# stm32_ULN2003a.net
KiCad netlist of a schematic drawn in EasyEDA Pro
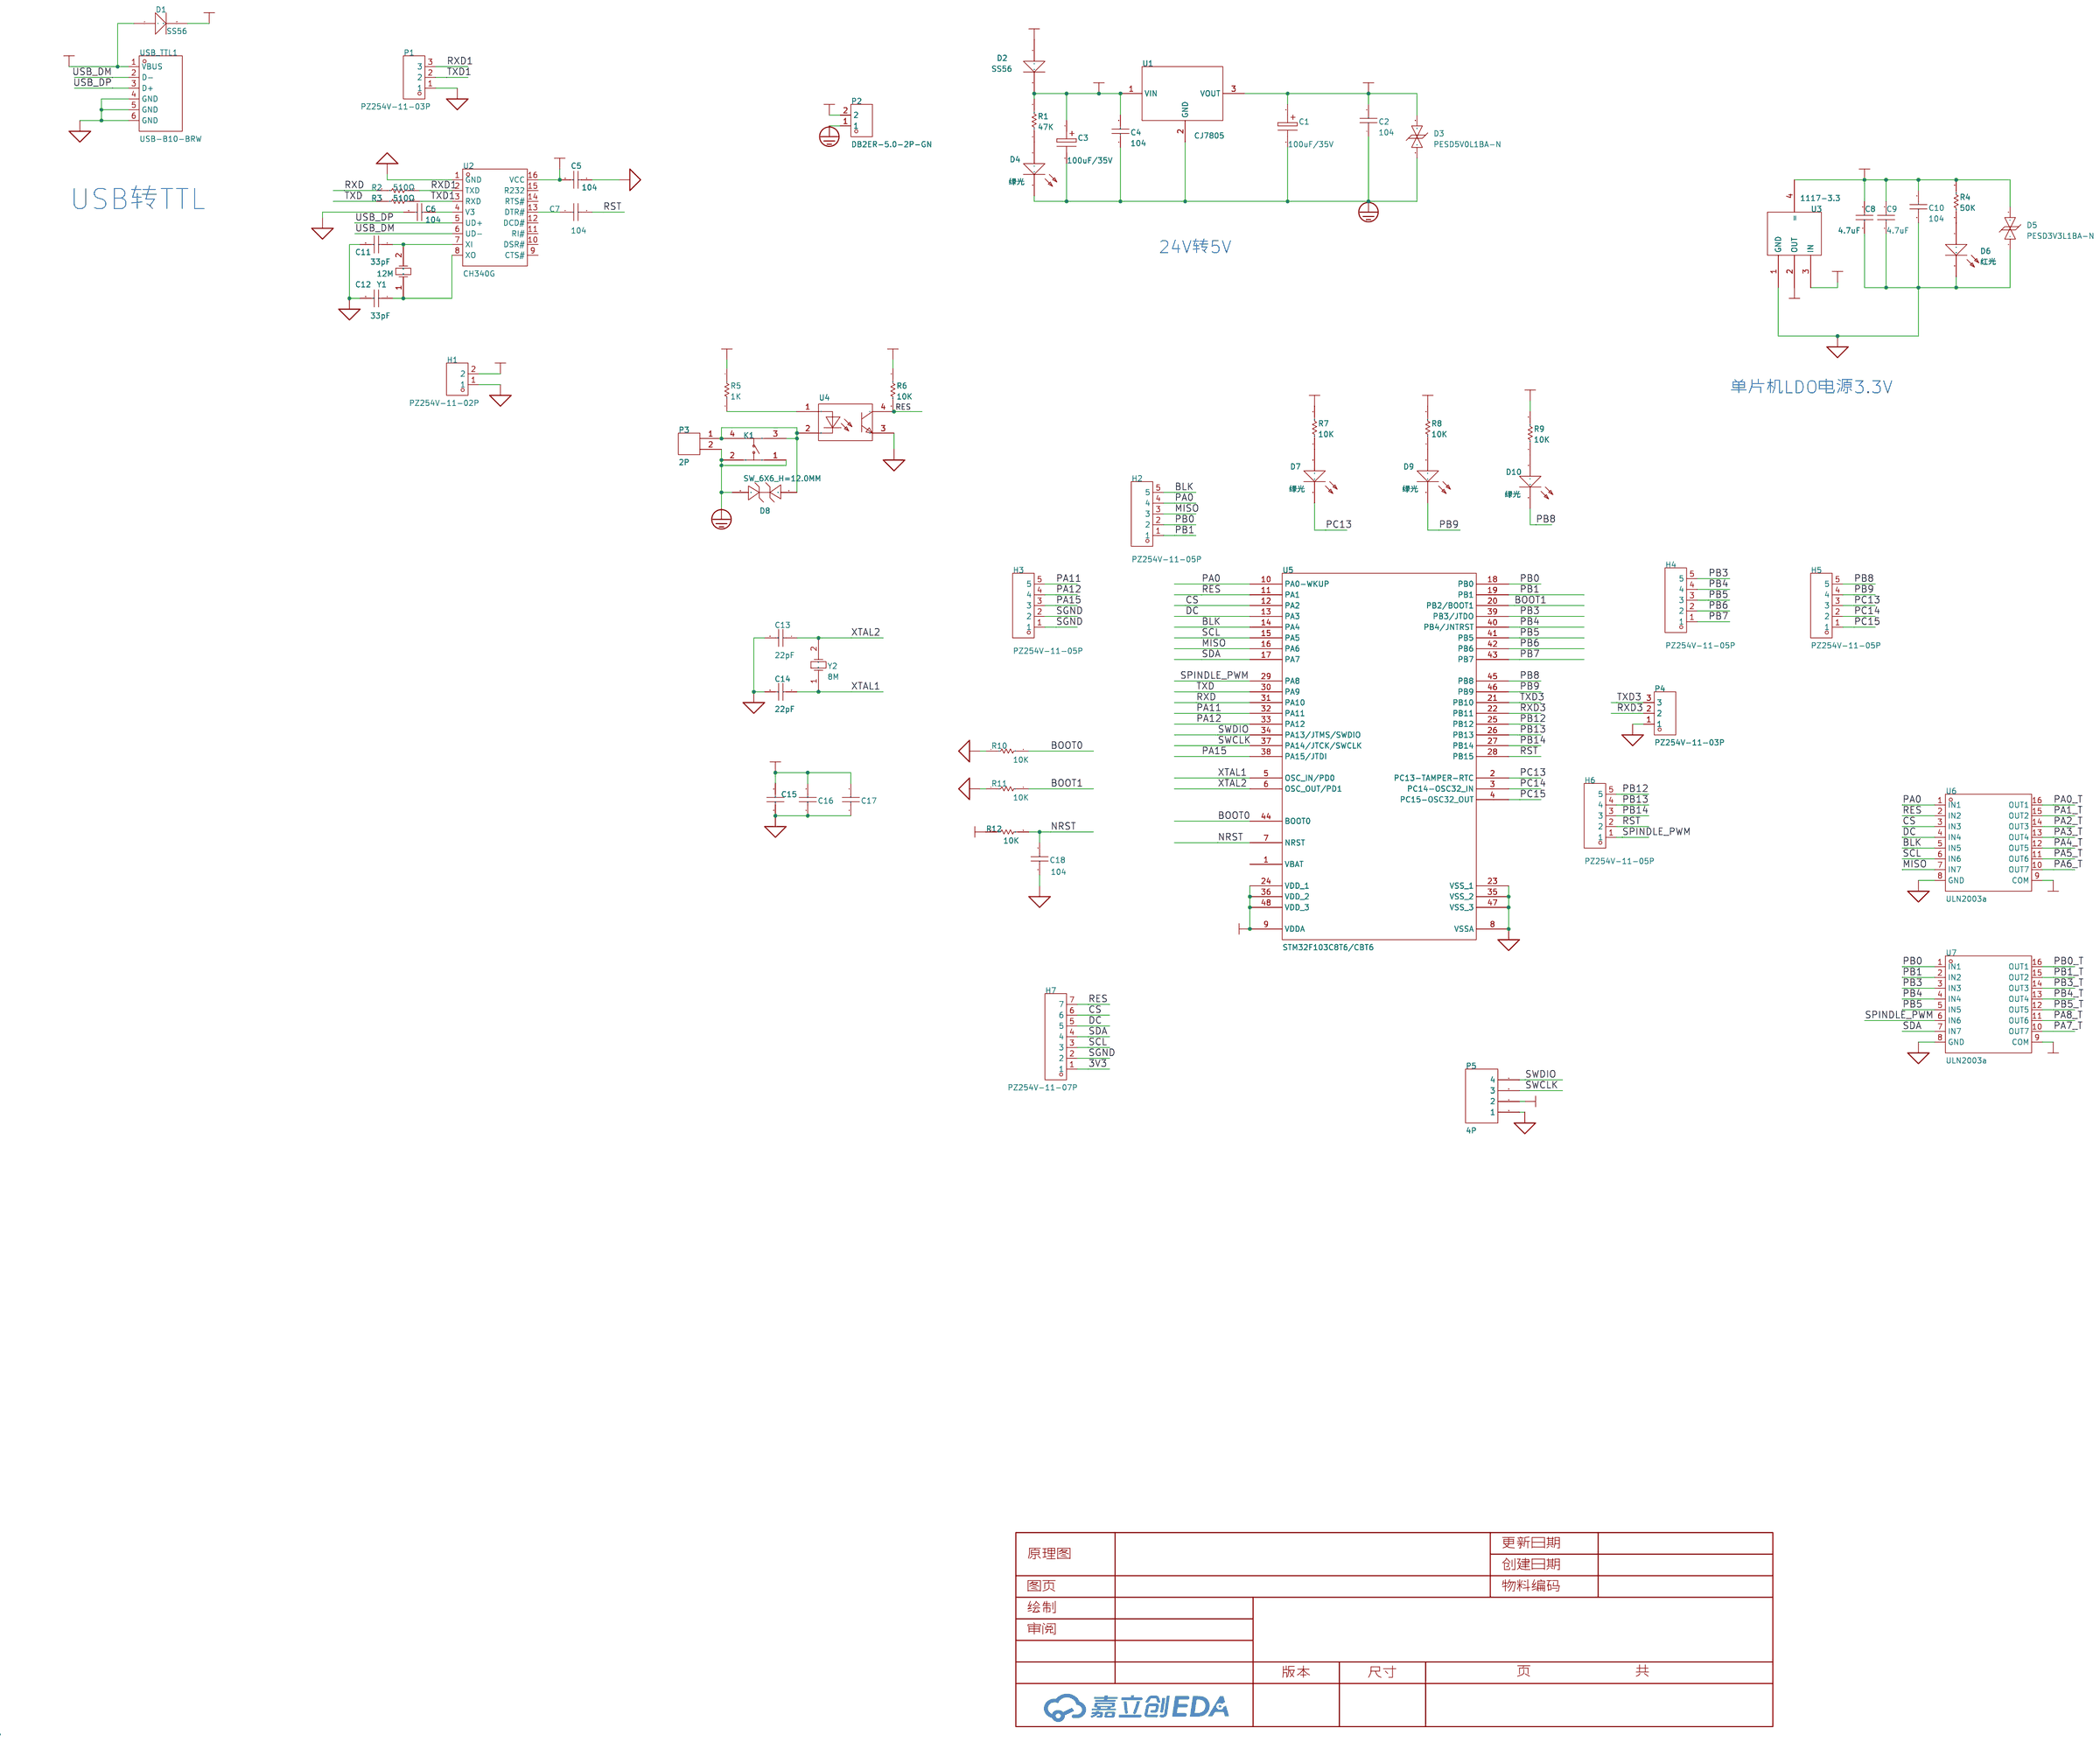
[diagram p0: 主控MCU]
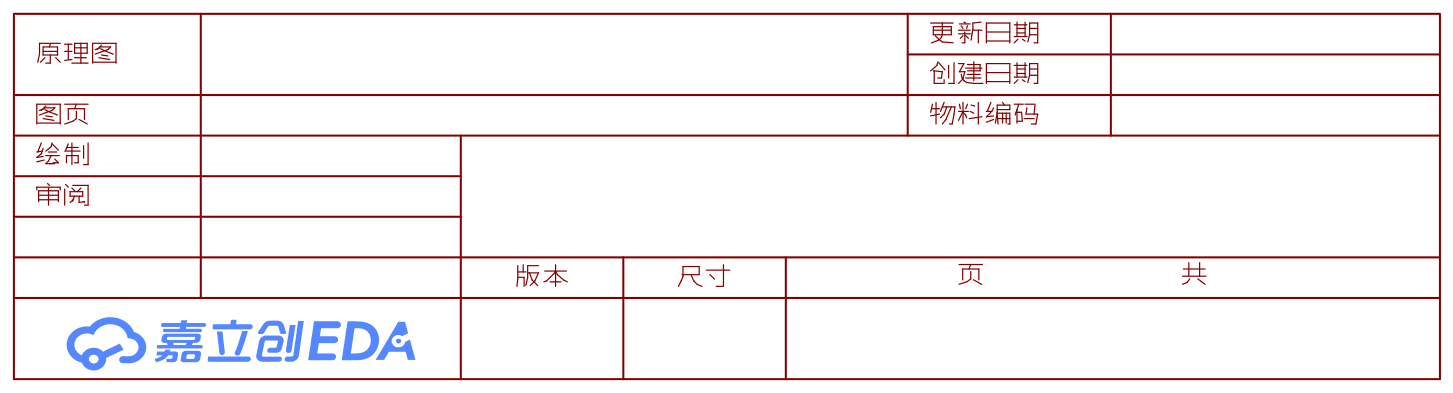
[diagram p1: 电源及控制]

(export (version "E")
  (design (tool "Eeschema 10.0.6"))
  (components
    (comp (ref "C1")
      (value "100uF/35V")
      (footprint "easyedapro:0603C")
      (libsource (lib "easyedapro") (part "ELECTRO1"))
    )
    (comp (ref "C2")
      (value "104")
      (footprint "easyedapro:0603C")
      (description "Capacitor (Semiconductor SIM Model)")
      (libsource (lib "easyedapro") (part "Cap Semi"))
    )
    (comp (ref "C3")
      (value "100uF/35V")
      (footprint "easyedapro:0603C")
      (libsource (lib "easyedapro") (part "ELECTRO1"))
    )
    (comp (ref "C4")
      (value "104")
      (footprint "easyedapro:0603C")
      (description "Capacitor (Semiconductor SIM Model)")
      (libsource (lib "easyedapro") (part "Cap Semi"))
    )
    (comp (ref "C5")
      (value "104")
      (footprint "easyedapro:0603C")
      (description "Capacitor (Semiconductor SIM Model)")
      (libsource (lib "easyedapro") (part "Cap Semi"))
    )
    (comp (ref "C6")
      (value "104")
      (footprint "easyedapro:0603C")
      (description "Capacitor (Semiconductor SIM Model)")
      (libsource (lib "easyedapro") (part "Cap Semi"))
    )
    (comp (ref "C7")
      (value "104")
      (footprint "easyedapro:0603C")
      (description "Capacitor (Semiconductor SIM Model)")
      (libsource (lib "easyedapro") (part "Cap Semi"))
    )
    (comp (ref "C8") (value "4.7uF") (libsource (lib "easyedapro") (part "CAP")))
    (comp (ref "C9") (value "4.7uF") (libsource (lib "easyedapro") (part "CAP")))
    (comp (ref "C10")
      (value "104")
      (footprint "easyedapro:0603C")
      (description "Capacitor (Semiconductor SIM Model)")
      (libsource (lib "easyedapro") (part "Cap Semi"))
    )
    (comp (ref "C11")
      (value "18pF")
      (footprint "easyedapro:0603C")
      (description "Capacitor (Semiconductor SIM Model)")
      (libsource (lib "easyedapro") (part "Cap Semi"))
    )
    (comp (ref "C12")
      (value "18pF")
      (footprint "easyedapro:0603C")
      (description "Capacitor (Semiconductor SIM Model)")
      (libsource (lib "easyedapro") (part "Cap Semi"))
    )
    (comp (ref "C13")
      (value "100pF")
      (footprint "easyedapro:0603C")
      (description "Capacitor (Semiconductor SIM Model)")
      (libsource (lib "easyedapro") (part "Cap Semi"))
    )
    (comp (ref "C14")
      (value "100pF")
      (footprint "easyedapro:0603C")
      (description "Capacitor (Semiconductor SIM Model)")
      (libsource (lib "easyedapro") (part "Cap Semi"))
    )
    (comp (ref "C15") (value "104") (footprint "easyedapro:电解电容贴片6X6") (libsource (lib "") (part "CAP_1")))
    (comp (ref "C16") (value "104") (footprint "easyedapro:电解电容贴片6X6") (libsource (lib "") (part "CAP_1")))
    (comp (ref "C17") (value "104") (footprint "easyedapro:电解电容贴片6X6") (libsource (lib "") (part "CAP_1")))
    (comp (ref "C18")
      (value "104")
      (footprint "easyedapro:0603C")
      (description "Capacitor (Semiconductor SIM Model)")
      (libsource (lib "easyedapro") (part "Cap Semi"))
    )
    (comp (ref "D1")
      (value "SS56")
      (footprint "easyedapro:SMA")
      (libsource (lib "easyedapro") (part "1N4148"))
    )
    (comp (ref "D2")
      (value "SS56")
      (footprint "easyedapro:SMA")
      (libsource (lib "easyedapro") (part "1N4148"))
    )
    (comp (ref "D3")
      (value "PESD5V0L1BA-N")
      (footprint "easyedapro:SOD-523_L1.2-W0.8-LS1.6-BI")
      (description "极性:Bidirectional;反向关断电压（典型值）:5V (Max);击穿电压（最小值）:6V;箝位电压:15V;峰值脉冲电流（10/1000us）:5A (8/20us);")
      (fields (field (name "Manufacturer") "BORN伯恩半导体"))
      (libsource (lib "easyedapro") (part "PESD5V0S1BBN"))
    )
    (comp (ref "D4")
      (value "绿光")
      (footprint "easyedapro:0603LED")
      (libsource (lib "easyedapro") (part "LED"))
    )
    (comp (ref "D5")
      (value "PESD3V3L1BA-N")
      (footprint "easyedapro:SOD-523_L1.2-W0.8-LS1.6-BI")
      (description "极性:Bidirectional;反向关断电压（典型值）:5V (Max);击穿电压（最小值）:6V;箝位电压:15V;峰值脉冲电流（10/1000us）:5A (8/20us);")
      (fields (field (name "Manufacturer") "BORN伯恩半导体"))
      (libsource (lib "easyedapro") (part "PESD5V0S1BBN"))
    )
    (comp (ref "D6")
      (value "红光")
      (footprint "easyedapro:0603LED")
      (libsource (lib "easyedapro") (part "LED"))
    )
    (comp (ref "D7")
      (value "绿光")
      (footprint "easyedapro:0603LED")
      (libsource (lib "easyedapro") (part "LED"))
    )
    (comp (ref "D8")
      (value "ESD05V52D-C")
      (footprint "easyedapro:SOD-523_L1.2-W0.8-LS1.6-BI")
      (fields (field (name "Manufacturer") "TWGMC(台湾迪嘉)"))
      (libsource (lib "easyedapro") (part "ESD05V52D-C"))
    )
    (comp (ref "D9")
      (value "绿光")
      (footprint "easyedapro:0603LED")
      (libsource (lib "easyedapro") (part "LED"))
    )
    (comp (ref "D10")
      (value "绿光")
      (footprint "easyedapro:0603LED")
      (libsource (lib "easyedapro") (part "LED"))
    )
    (comp (ref "H1")
      (value "PZ254V-11-02P")
      (footprint "easyedapro:HDR-TH_2P-P2.54-V-M")
      (fields (field (name "Manufacturer") "XFCN(兴飞)"))
      (libsource (lib "easyedapro") (part "PZ254V-11-02P"))
    )
    (comp (ref "H2")
      (value "PZ254V-11-05P")
      (footprint "easyedapro:HDR-TH_5P-P2.54-V-M")
      (fields (field (name "Manufacturer") "XFCN(兴飞)"))
      (libsource (lib "easyedapro") (part "PZ254V-11-05P"))
    )
    (comp (ref "H3")
      (value "PZ254V-11-05P")
      (footprint "easyedapro:HDR-TH_5P-P2.54-V-M")
      (fields (field (name "Manufacturer") "XFCN(兴飞)"))
      (libsource (lib "easyedapro") (part "PZ254V-11-05P"))
    )
    (comp (ref "H4")
      (value "PZ254V-11-05P")
      (footprint "easyedapro:HDR-TH_5P-P2.54-V-M")
      (fields (field (name "Manufacturer") "XFCN(兴飞)"))
      (libsource (lib "easyedapro") (part "PZ254V-11-05P"))
    )
    (comp (ref "H5")
      (value "PZ254V-11-05P")
      (footprint "easyedapro:HDR-TH_5P-P2.54-V-M")
      (fields (field (name "Manufacturer") "XFCN(兴飞)"))
      (libsource (lib "easyedapro") (part "PZ254V-11-05P"))
    )
    (comp (ref "H6")
      (value "PZ254V-11-05P")
      (footprint "easyedapro:HDR-TH_5P-P2.54-V-M")
      (fields (field (name "Manufacturer") "XFCN(兴飞)"))
      (libsource (lib "easyedapro") (part "PZ254V-11-05P"))
    )
    (comp (ref "H7")
      (value "PZ254V-11-07P")
      (footprint "easyedapro:HDR-TH_7P-P2.54-V-M")
      (fields (field (name "Manufacturer") "XFCN(兴飞)"))
      (libsource (lib "easyedapro") (part "PZ254V-11-07P"))
    )
    (comp (ref "K1")
      (value "SW_6X6_H=12.0MM")
      (footprint "easyedapro:KEY-SMD_4P-L6.0-W6.0-P4.50-LS9.0")
      (libsource (lib "easyedapro") (part "SW_6X6_H=12.0MM"))
    )
    (comp (ref "P1")
      (value "PZ254V-11-03P")
      (footprint "easyedapro:HDR-TH_3P-P2.54-V-M")
      (fields (field (name "Manufacturer") "XFCN(兴飞)"))
      (libsource (lib "easyedapro") (part "PZ254V-11-03P_C2937625"))
    )
    (comp (ref "P2")
      (value "DB2ER-5.0-2P-GN")
      (footprint "easyedapro:CONN-TH_2P-P5.00_DB2ER-5.0-2P-GN")
      (description "间距:5mm;颜色:绿色;排数:1;每排PIN数:2;额定电流:15A;额定电压:630V;触头镀层:锡;")
      (fields (field (name "Manufacturer") "DORABO(地博电气)"))
      (libsource (lib "easyedapro") (part "DB2ER-5.0-2P-GN"))
    )
    (comp (ref "P3") (value "2P") (libsource (lib "easyedapro") (part "2P")))
    (comp (ref "P4")
      (value "PZ254V-11-03P")
      (footprint "easyedapro:HDR-TH_3P-P2.54-V-M")
      (fields (field (name "Manufacturer") "XFCN(兴飞)"))
      (libsource (lib "easyedapro") (part "PZ254V-11-03P_C2937625"))
    )
    (comp (ref "P5") (value "4P") (libsource (lib "easyedapro") (part "4P")))
    (comp (ref "R1")
      (value "47K")
      (footprint "easyedapro:0603R")
      (description "Resistor")
      (libsource (lib "easyedapro") (part "RES"))
    )
    (comp (ref "R2")
      (value "510Ω")
      (footprint "easyedapro:0603R")
      (description "Resistor")
      (libsource (lib "easyedapro") (part "RES"))
    )
    (comp (ref "R3")
      (value "510Ω")
      (footprint "easyedapro:0603R")
      (description "Resistor")
      (libsource (lib "easyedapro") (part "RES"))
    )
    (comp (ref "R4")
      (value "50K")
      (footprint "easyedapro:0603R")
      (description "Resistor")
      (libsource (lib "easyedapro") (part "RES"))
    )
    (comp (ref "R5")
      (value "1K")
      (footprint "easyedapro:0603R")
      (description "Resistor")
      (libsource (lib "easyedapro") (part "RES"))
    )
    (comp (ref "R6")
      (value "10K")
      (footprint "easyedapro:0603R")
      (description "Resistor")
      (libsource (lib "easyedapro") (part "RES"))
    )
    (comp (ref "R7")
      (value "10K")
      (footprint "easyedapro:0603R")
      (description "Resistor")
      (libsource (lib "easyedapro") (part "RES"))
    )
    (comp (ref "R8")
      (value "10K")
      (footprint "easyedapro:0603R")
      (description "Resistor")
      (libsource (lib "easyedapro") (part "RES"))
    )
    (comp (ref "R9")
      (value "10K")
      (footprint "easyedapro:0603R")
      (description "Resistor")
      (libsource (lib "easyedapro") (part "RES"))
    )
    (comp (ref "R10")
      (value "10K")
      (footprint "easyedapro:0603R")
      (description "Resistor")
      (libsource (lib "easyedapro") (part "RES"))
    )
    (comp (ref "R11")
      (value "10K")
      (footprint "easyedapro:0603R")
      (description "Resistor")
      (libsource (lib "easyedapro") (part "RES"))
    )
    (comp (ref "R12")
      (value "10K")
      (footprint "easyedapro:0603R")
      (description "Resistor")
      (libsource (lib "easyedapro") (part "RES"))
    )
    (comp (ref "U1")
      (value "CJ7805")
      (footprint "easyedapro:TO-263-2")
      (libsource (lib "easyedapro") (part "7805"))
    )
    (comp (ref "U2")
      (value "CH340G")
      (footprint "easyedapro:SOIC-16_L9.9-W3.9-P1.27-LS6.0-BL")
      (description "应用功能:收发器;接口协议:USB 2.0;数据速率:2Mbps;")
      (fields (field (name "Manufacturer") "WCH(南京沁恒)"))
      (libsource (lib "easyedapro") (part "CH340G"))
    )
    (comp (ref "U3")
      (value "1117-3.3")
      (footprint "easyedapro:SOT-223")
      (libsource (lib "easyedapro") (part "LM1117"))
    )
    (comp (ref "U4")
      (value "LTV-357T-C")
      (footprint "easyedapro:SOP-4_L4.4-W3.9-P2.54-LS7.0-TL")
      (fields (field (name "Manufacturer") "LITEON(光宝)"))
      (libsource (lib "easyedapro") (part "LTV-357T-C"))
    )
    (comp (ref "U5")
      (value "STM32F103C8T6/CBT6")
      (footprint "easyedapro:LQFP48")
      (description "STM32 ARM-based 32-bit MCU with 32 Kbytes Flash, 48-pin LQFP, Industrial Temperature")
      (libsource (lib "easyedapro") (part "STM32F103C6T6"))
    )
    (comp (ref "U6")
      (value "ULN2003a")
      (footprint "easyedapro:SOP-16_L9.9-W3.9-P1.27-LS6.0-BL")
      (description "通道数:七路;集射击穿电压(Vceo):50V;集电极电流(Ic):500mA;")
      (fields (field (name "Manufacturer") "GR(国睿)"))
      (libsource (lib "easyedapro") (part "ULN2003_C18164408"))
    )
    (comp (ref "U7")
      (value "ULN2003a")
      (footprint "easyedapro:SOP-16_L9.9-W3.9-P1.27-LS6.0-BL")
      (description "通道数:七路;集射击穿电压(Vceo):50V;集电极电流(Ic):500mA;")
      (fields (field (name "Manufacturer") "GR(国睿)"))
      (libsource (lib "easyedapro") (part "ULN2003_C18164408"))
    )
    (comp (ref "USB_TTL1")
      (value "USB-B10-BRW")
      (footprint "easyedapro:USB-B-TH_USB-B10-BRW")
      (fields (field (name "Manufacturer") "XUNPU(讯普)"))
      (libsource (lib "easyedapro") (part "USB-B10-BRW"))
    )
    (comp (ref "Y1")
      (value "12M")
      (footprint "easyedapro:晶振贴片49SSMD")
      (description "Crystal Oscillator")
      (libsource (lib "easyedapro") (part "XTAL"))
    )
    (comp (ref "Y2")
      (value "8M")
      (footprint "easyedapro:晶振贴片49SSMD")
      (description "Crystal Oscillator")
      (libsource (lib "easyedapro") (part "XTAL"))
    )
  )
  (nets
    (net (code "1") (name "3V3") (class "Default")
      (node (ref "C10") (pin "2") (pinfunction "2_2") (pintype "unspecified"))
      (node (ref "C15") (pin "2") (pinfunction "2_2") (pintype "unspecified"))
      (node (ref "C16") (pin "2") (pinfunction "2_2") (pintype "unspecified"))
      (node (ref "C17") (pin "2") (pinfunction "2_2") (pintype "unspecified"))
      (node (ref "C8") (pin "2") (pinfunction "2_2") (pintype "input"))
      (node (ref "C9") (pin "2") (pinfunction "2_2") (pintype "input"))
      (node (ref "D5") (pin "2") (pinfunction "2_2") (pintype "input"))
      (node (ref "H7") (pin "1") (pinfunction "1_1") (pintype "unspecified"))
      (node (ref "P5") (pin "2") (pinfunction "2_2") (pintype "input"))
      (node (ref "R12") (pin "1") (pinfunction "1_1") (pintype "unspecified"))
      (node (ref "R4") (pin "1") (pinfunction "1_1") (pintype "unspecified"))
      (node (ref "R6") (pin "1") (pinfunction "1_1") (pintype "unspecified"))
      (node (ref "R7") (pin "2") (pinfunction "2_2") (pintype "unspecified"))
      (node (ref "R8") (pin "2") (pinfunction "2_2") (pintype "unspecified"))
      (node (ref "R9") (pin "2") (pinfunction "2_2") (pintype "unspecified"))
      (node (ref "U3") (pin "2") (pinfunction "OUT_2") (pintype "unspecified"))
      (node (ref "U3") (pin "4") (pinfunction "=_4") (pintype "unspecified"))
      (node (ref "U5") (pin "24") (pinfunction "VDD_1_24") (pintype "unspecified"))
      (node (ref "U5") (pin "36") (pinfunction "VDD_2_36") (pintype "unspecified"))
      (node (ref "U5") (pin "48") (pinfunction "VDD_3_48") (pintype "unspecified"))
      (node (ref "U5") (pin "9") (pinfunction "VDDA_9") (pintype "unspecified"))
    )
    (net (code "2") (name "5V_VCC") (class "Default")
      (node (ref "C1") (pin "1") (pintype "unspecified"))
      (node (ref "C2") (pin "2") (pinfunction "2_2") (pintype "unspecified"))
      (node (ref "C5") (pin "2") (pinfunction "2_2") (pintype "unspecified"))
      (node (ref "D1") (pin "2") (pinfunction "2_2") (pintype "unspecified"))
      (node (ref "D3") (pin "2") (pinfunction "2_2") (pintype "input"))
      (node (ref "H1") (pin "2") (pinfunction "2_2") (pintype "unspecified"))
      (node (ref "R5") (pin "1") (pinfunction "1_1") (pintype "unspecified"))
      (node (ref "U1") (pin "3") (pinfunction "VOUT_3") (pintype "unspecified"))
      (node (ref "U2") (pin "16") (pinfunction "VCC_16") (pintype "unspecified"))
      (node (ref "U3") (pin "3") (pinfunction "IN_3") (pintype "unspecified"))
      (node (ref "U6") (pin "9") (pinfunction "COM_9") (pintype "unspecified"))
      (node (ref "U7") (pin "9") (pinfunction "COM_9") (pintype "unspecified"))
    )
    (net (code "3") (name "24V") (class "Default")
      (node (ref "D2") (pin "1") (pinfunction "1_1") (pintype "unspecified"))
      (node (ref "P2") (pin "2") (pinfunction "2_2") (pintype "unspecified"))
    )
    (net (code "4") (name "BLK") (class "Default")
      (node (ref "H2") (pin "5") (pinfunction "5_5") (pintype "input"))
      (node (ref "U5") (pin "14") (pinfunction "PA4_14") (pintype "bidirectional"))
      (node (ref "U6") (pin "5") (pinfunction "IN5_5") (pintype "unspecified"))
    )
    (net (code "5") (name "BOOT0") (class "Default")
      (node (ref "R10") (pin "2") (pinfunction "2_2") (pintype "unspecified"))
      (node (ref "U5") (pin "44") (pinfunction "BOOT0_44") (pintype "input"))
    )
    (net (code "6") (name "BOOT1") (class "Default")
      (node (ref "R11") (pin "2") (pinfunction "2_2") (pintype "unspecified"))
      (node (ref "U5") (pin "20") (pinfunction "PB2/BOOT1_20") (pintype "bidirectional"))
    )
    (net (code "7") (name "CS") (class "Default")
      (node (ref "H7") (pin "6") (pinfunction "6_6") (pintype "unspecified"))
      (node (ref "U5") (pin "12") (pinfunction "PA2_12") (pintype "bidirectional"))
      (node (ref "U6") (pin "3") (pinfunction "IN3_3") (pintype "unspecified"))
    )
    (net (code "8") (name "DC") (class "Default")
      (node (ref "H7") (pin "5") (pinfunction "5_5") (pintype "unspecified"))
      (node (ref "U5") (pin "13") (pinfunction "PA3_13") (pintype "bidirectional"))
      (node (ref "U6") (pin "4") (pinfunction "IN4_4") (pintype "unspecified"))
    )
    (net (code "9") (name "MISO") (class "Default")
      (node (ref "H2") (pin "3") (pinfunction "3_3") (pintype "input"))
      (node (ref "U5") (pin "16") (pinfunction "PA6_16") (pintype "bidirectional"))
      (node (ref "U6") (pin "7") (pinfunction "IN7_7") (pintype "unspecified"))
    )
    (net (code "10") (name "NRST") (class "Default")
      (node (ref "C18") (pin "2") (pinfunction "2_2") (pintype "unspecified"))
      (node (ref "R12") (pin "2") (pinfunction "2_2") (pintype "unspecified"))
      (node (ref "U5") (pin "7") (pinfunction "NRST_7") (pintype "bidirectional"))
    )
    (net (code "11") (name "Net-(D4-Pad1)") (class "Default")
      (node (ref "D4") (pin "1") (pinfunction "1_1") (pintype "unspecified"))
      (node (ref "R1") (pin "1") (pinfunction "1_1") (pintype "unspecified"))
    )
    (net (code "12") (name "Net-(D6-Pad1)") (class "Default")
      (node (ref "D6") (pin "1") (pinfunction "1_1") (pintype "unspecified"))
      (node (ref "R4") (pin "2") (pinfunction "2_2") (pintype "unspecified"))
    )
    (net (code "13") (name "Net-(D7-Pad1)") (class "Default")
      (node (ref "D7") (pin "1") (pinfunction "1_1") (pintype "unspecified"))
      (node (ref "R7") (pin "1") (pinfunction "1_1") (pintype "unspecified"))
    )
    (net (code "14") (name "Net-(D8-Pad2)") (class "Default")
      (node (ref "D8") (pin "2") (pinfunction "2_2") (pintype "unspecified"))
      (node (ref "K1") (pin "3") (pinfunction "3_3") (pintype "unspecified"))
      (node (ref "K1") (pin "4") (pinfunction "4_4") (pintype "unspecified"))
      (node (ref "P3") (pin "1") (pintype "input"))
      (node (ref "U4") (pin "2") (pinfunction "2_2") (pintype "unspecified"))
    )
    (net (code "15") (name "Net-(D9-Pad1)") (class "Default")
      (node (ref "D9") (pin "1") (pinfunction "1_1") (pintype "unspecified"))
      (node (ref "R8") (pin "1") (pinfunction "1_1") (pintype "unspecified"))
    )
    (net (code "16") (name "Net-(D10-Pad1)") (class "Default")
      (node (ref "D10") (pin "1") (pinfunction "1_1") (pintype "unspecified"))
      (node (ref "R9") (pin "1") (pinfunction "1_1") (pintype "unspecified"))
    )
    (net (code "17") (name "Net-(R5-Pad2)") (class "Default")
      (node (ref "R5") (pin "2") (pinfunction "2_2") (pintype "unspecified"))
      (node (ref "U4") (pin "1") (pinfunction "1_1") (pintype "unspecified"))
    )
    (net (code "18") (name "Net-(U2-DTR#)") (class "Default")
      (node (ref "C7") (pin "1") (pinfunction "1_1") (pintype "unspecified"))
      (node (ref "U2") (pin "13") (pinfunction "DTR#_13") (pintype "unspecified"))
    )
    (net (code "19") (name "Net-(U2-V3)") (class "Default")
      (node (ref "C6") (pin "1") (pinfunction "1_1") (pintype "unspecified"))
      (node (ref "U2") (pin "4") (pinfunction "V3_4") (pintype "unspecified"))
    )
    (net (code "20") (name "Net-(U2-XI)") (class "Default")
      (node (ref "C11") (pin "1") (pinfunction "1_1") (pintype "unspecified"))
      (node (ref "U2") (pin "7") (pinfunction "XI_7") (pintype "unspecified"))
      (node (ref "Y1") (pin "2") (pinfunction "OSC2_2") (pintype "unspecified"))
    )
    (net (code "21") (name "Net-(U2-XO)") (class "Default")
      (node (ref "C12") (pin "1") (pinfunction "1_1") (pintype "unspecified"))
      (node (ref "U2") (pin "8") (pinfunction "XO_8") (pintype "unspecified"))
      (node (ref "Y1") (pin "1") (pinfunction "OSC1_1") (pintype "unspecified"))
    )
    (net (code "22") (name "PA0") (class "Default")
      (node (ref "H2") (pin "4") (pinfunction "4_4") (pintype "input"))
      (node (ref "U5") (pin "10") (pinfunction "PA0-WKUP_10") (pintype "bidirectional"))
      (node (ref "U6") (pin "1") (pinfunction "IN1_1") (pintype "unspecified"))
    )
    (net (code "23") (name "PA0_T") (class "Default")
      (node (ref "U6") (pin "16") (pinfunction "OUT1_16") (pintype "unspecified"))
    )
    (net (code "24") (name "PA1_T") (class "Default")
      (node (ref "U6") (pin "15") (pinfunction "OUT2_15") (pintype "unspecified"))
    )
    (net (code "25") (name "PA2_T") (class "Default")
      (node (ref "U6") (pin "14") (pinfunction "OUT3_14") (pintype "unspecified"))
    )
    (net (code "26") (name "PA3_T") (class "Default")
      (node (ref "U6") (pin "13") (pinfunction "OUT4_13") (pintype "unspecified"))
    )
    (net (code "27") (name "PA4_T") (class "Default")
      (node (ref "U6") (pin "12") (pinfunction "OUT5_12") (pintype "unspecified"))
    )
    (net (code "28") (name "PA5_T") (class "Default")
      (node (ref "U6") (pin "11") (pinfunction "OUT6_11") (pintype "unspecified"))
    )
    (net (code "29") (name "PA6_T") (class "Default")
      (node (ref "U6") (pin "10") (pinfunction "OUT7_10") (pintype "unspecified"))
    )
    (net (code "30") (name "PA7_T") (class "Default")
      (node (ref "U7") (pin "10") (pinfunction "OUT7_10") (pintype "unspecified"))
    )
    (net (code "31") (name "PA8_T") (class "Default")
      (node (ref "U7") (pin "11") (pinfunction "OUT6_11") (pintype "unspecified"))
    )
    (net (code "32") (name "PA11") (class "Default")
      (node (ref "H3") (pin "5") (pinfunction "5_5") (pintype "input"))
      (node (ref "U5") (pin "32") (pinfunction "PA11_32") (pintype "bidirectional"))
    )
    (net (code "33") (name "PA12") (class "Default")
      (node (ref "H3") (pin "4") (pinfunction "4_4") (pintype "input"))
      (node (ref "U5") (pin "33") (pinfunction "PA12_33") (pintype "bidirectional"))
    )
    (net (code "34") (name "PA15") (class "Default")
      (node (ref "H3") (pin "3") (pinfunction "3_3") (pintype "input"))
      (node (ref "U5") (pin "38") (pinfunction "PA15/JTDI_38") (pintype "bidirectional"))
    )
    (net (code "35") (name "PB0") (class "Default")
      (node (ref "H2") (pin "2") (pinfunction "2_2") (pintype "input"))
      (node (ref "U5") (pin "18") (pinfunction "PB0_18") (pintype "bidirectional"))
      (node (ref "U7") (pin "1") (pinfunction "IN1_1") (pintype "unspecified"))
    )
    (net (code "36") (name "PB0_T") (class "Default")
      (node (ref "U7") (pin "16") (pinfunction "OUT1_16") (pintype "unspecified"))
    )
    (net (code "37") (name "PB1") (class "Default")
      (node (ref "H2") (pin "1") (pinfunction "1_1") (pintype "input"))
      (node (ref "U5") (pin "19") (pinfunction "PB1_19") (pintype "bidirectional"))
      (node (ref "U7") (pin "2") (pinfunction "IN2_2") (pintype "unspecified"))
    )
    (net (code "38") (name "PB1_T") (class "Default")
      (node (ref "U7") (pin "15") (pinfunction "OUT2_15") (pintype "unspecified"))
    )
    (net (code "39") (name "PB3") (class "Default")
      (node (ref "H4") (pin "5") (pinfunction "5_5") (pintype "input"))
      (node (ref "U5") (pin "39") (pinfunction "PB3/JTDO_39") (pintype "bidirectional"))
      (node (ref "U7") (pin "3") (pinfunction "IN3_3") (pintype "unspecified"))
    )
    (net (code "40") (name "PB3_T") (class "Default")
      (node (ref "U7") (pin "14") (pinfunction "OUT3_14") (pintype "unspecified"))
    )
    (net (code "41") (name "PB4") (class "Default")
      (node (ref "H4") (pin "4") (pinfunction "4_4") (pintype "input"))
      (node (ref "U5") (pin "40") (pinfunction "PB4/JNTRST_40") (pintype "bidirectional"))
      (node (ref "U7") (pin "4") (pinfunction "IN4_4") (pintype "unspecified"))
    )
    (net (code "42") (name "PB4_T") (class "Default")
      (node (ref "U7") (pin "13") (pinfunction "OUT4_13") (pintype "unspecified"))
    )
    (net (code "43") (name "PB5") (class "Default")
      (node (ref "H4") (pin "3") (pinfunction "3_3") (pintype "input"))
      (node (ref "U5") (pin "41") (pinfunction "PB5_41") (pintype "bidirectional"))
      (node (ref "U7") (pin "5") (pinfunction "IN5_5") (pintype "unspecified"))
    )
    (net (code "44") (name "PB5_T") (class "Default")
      (node (ref "U7") (pin "12") (pinfunction "OUT5_12") (pintype "unspecified"))
    )
    (net (code "45") (name "PB6") (class "Default")
      (node (ref "H4") (pin "2") (pinfunction "2_2") (pintype "input"))
      (node (ref "U5") (pin "42") (pinfunction "PB6_42") (pintype "bidirectional"))
    )
    (net (code "46") (name "PB7") (class "Default")
      (node (ref "H4") (pin "1") (pinfunction "1_1") (pintype "input"))
      (node (ref "U5") (pin "43") (pinfunction "PB7_43") (pintype "bidirectional"))
    )
    (net (code "47") (name "PB8") (class "Default")
      (node (ref "D10") (pin "2") (pinfunction "2_2") (pintype "unspecified"))
      (node (ref "H5") (pin "5") (pinfunction "5_5") (pintype "input"))
      (node (ref "U5") (pin "45") (pinfunction "PB8_45") (pintype "bidirectional"))
    )
    (net (code "48") (name "PB9") (class "Default")
      (node (ref "D9") (pin "2") (pinfunction "2_2") (pintype "unspecified"))
      (node (ref "H5") (pin "4") (pinfunction "4_4") (pintype "input"))
      (node (ref "U5") (pin "46") (pinfunction "PB9_46") (pintype "bidirectional"))
    )
    (net (code "49") (name "PB12") (class "Default")
      (node (ref "H6") (pin "5") (pinfunction "5_5") (pintype "input"))
      (node (ref "U5") (pin "25") (pinfunction "PB12_25") (pintype "bidirectional"))
    )
    (net (code "50") (name "PB13") (class "Default")
      (node (ref "H6") (pin "4") (pinfunction "4_4") (pintype "input"))
      (node (ref "U5") (pin "26") (pinfunction "PB13_26") (pintype "bidirectional"))
    )
    (net (code "51") (name "PB14") (class "Default")
      (node (ref "H6") (pin "3") (pinfunction "3_3") (pintype "input"))
      (node (ref "U5") (pin "27") (pinfunction "PB14_27") (pintype "bidirectional"))
    )
    (net (code "52") (name "PC13") (class "Default")
      (node (ref "D7") (pin "2") (pinfunction "2_2") (pintype "unspecified"))
      (node (ref "H5") (pin "3") (pinfunction "3_3") (pintype "input"))
      (node (ref "U5") (pin "2") (pinfunction "PC13-TAMPER-RTC_2") (pintype "bidirectional"))
    )
    (net (code "53") (name "PC14") (class "Default")
      (node (ref "H5") (pin "2") (pinfunction "2_2") (pintype "input"))
      (node (ref "U5") (pin "3") (pinfunction "PC14-OSC32_IN_3") (pintype "bidirectional"))
    )
    (net (code "54") (name "PC15") (class "Default")
      (node (ref "H5") (pin "1") (pinfunction "1_1") (pintype "input"))
      (node (ref "U5") (pin "4") (pinfunction "PC15-OSC32_OUT_4") (pintype "bidirectional"))
    )
    (net (code "55") (name "RES") (class "Default")
      (node (ref "H7") (pin "7") (pinfunction "7_7") (pintype "unspecified"))
      (node (ref "R6") (pin "2") (pinfunction "2_2") (pintype "unspecified"))
      (node (ref "U4") (pin "4") (pinfunction "4_4") (pintype "unspecified"))
      (node (ref "U5") (pin "11") (pinfunction "PA1_11") (pintype "bidirectional"))
      (node (ref "U6") (pin "2") (pinfunction "IN2_2") (pintype "unspecified"))
    )
    (net (code "56") (name "RST") (class "Default")
      (node (ref "C7") (pin "2") (pinfunction "2_2") (pintype "unspecified"))
      (node (ref "H6") (pin "2") (pinfunction "2_2") (pintype "input"))
      (node (ref "U5") (pin "28") (pinfunction "PB15_28") (pintype "bidirectional"))
    )
    (net (code "57") (name "RXD") (class "Default")
      (node (ref "R2") (pin "2") (pinfunction "2_2") (pintype "unspecified"))
      (node (ref "U5") (pin "31") (pinfunction "PA10_31") (pintype "bidirectional"))
    )
    (net (code "58") (name "RXD1") (class "Default")
      (node (ref "P1") (pin "3") (pinfunction "3_3") (pintype "unspecified"))
      (node (ref "R2") (pin "1") (pinfunction "1_1") (pintype "unspecified"))
      (node (ref "U2") (pin "2") (pinfunction "TXD_2") (pintype "unspecified"))
    )
    (net (code "59") (name "RXD3") (class "Default")
      (node (ref "P4") (pin "2") (pinfunction "2_2") (pintype "unspecified"))
      (node (ref "U5") (pin "22") (pinfunction "PB11_22") (pintype "bidirectional"))
    )
    (net (code "60") (name "SCL") (class "Default")
      (node (ref "H7") (pin "3") (pinfunction "3_3") (pintype "unspecified"))
      (node (ref "U5") (pin "15") (pinfunction "PA5_15") (pintype "bidirectional"))
      (node (ref "U6") (pin "6") (pinfunction "IN6_6") (pintype "unspecified"))
    )
    (net (code "61") (name "SDA") (class "Default")
      (node (ref "H7") (pin "4") (pinfunction "4_4") (pintype "unspecified"))
      (node (ref "U5") (pin "17") (pinfunction "PA7_17") (pintype "bidirectional"))
      (node (ref "U7") (pin "7") (pinfunction "IN7_7") (pintype "unspecified"))
    )
    (net (code "62") (name "SGND") (class "Default")
      (node (ref "C1") (pin "2") (pintype "unspecified"))
      (node (ref "C10") (pin "1") (pinfunction "1_1") (pintype "unspecified"))
      (node (ref "C11") (pin "2") (pinfunction "2_2") (pintype "unspecified"))
      (node (ref "C12") (pin "2") (pinfunction "2_2") (pintype "unspecified"))
      (node (ref "C13") (pin "2") (pinfunction "2_2") (pintype "unspecified"))
      (node (ref "C14") (pin "2") (pinfunction "2_2") (pintype "unspecified"))
      (node (ref "C15") (pin "1") (pinfunction "1_1") (pintype "unspecified"))
      (node (ref "C16") (pin "1") (pinfunction "1_1") (pintype "unspecified"))
      (node (ref "C17") (pin "1") (pinfunction "1_1") (pintype "unspecified"))
      (node (ref "C18") (pin "1") (pinfunction "1_1") (pintype "unspecified"))
      (node (ref "C2") (pin "1") (pinfunction "1_1") (pintype "unspecified"))
      (node (ref "C3") (pin "2") (pintype "unspecified"))
      (node (ref "C4") (pin "1") (pinfunction "1_1") (pintype "unspecified"))
      (node (ref "C5") (pin "1") (pinfunction "1_1") (pintype "unspecified"))
      (node (ref "C6") (pin "2") (pinfunction "2_2") (pintype "unspecified"))
      (node (ref "C8") (pin "1") (pinfunction "1_1") (pintype "input"))
      (node (ref "C9") (pin "1") (pinfunction "1_1") (pintype "input"))
      (node (ref "D3") (pin "1") (pinfunction "1_1") (pintype "input"))
      (node (ref "D4") (pin "2") (pinfunction "2_2") (pintype "unspecified"))
      (node (ref "D5") (pin "1") (pinfunction "1_1") (pintype "input"))
      (node (ref "D6") (pin "2") (pinfunction "2_2") (pintype "unspecified"))
      (node (ref "D8") (pin "1") (pinfunction "1_1") (pintype "unspecified"))
      (node (ref "H1") (pin "1") (pinfunction "1_1") (pintype "unspecified"))
      (node (ref "H3") (pin "1") (pinfunction "1_1") (pintype "input"))
      (node (ref "H3") (pin "2") (pinfunction "2_2") (pintype "input"))
      (node (ref "H7") (pin "2") (pinfunction "2_2") (pintype "unspecified"))
      (node (ref "K1") (pin "1") (pinfunction "1_1") (pintype "unspecified"))
      (node (ref "K1") (pin "2") (pinfunction "2_2") (pintype "unspecified"))
      (node (ref "P1") (pin "1") (pinfunction "1_1") (pintype "unspecified"))
      (node (ref "P2") (pin "1") (pinfunction "1_1") (pintype "unspecified"))
      (node (ref "P3") (pin "2") (pintype "input"))
      (node (ref "P4") (pin "1") (pinfunction "1_1") (pintype "unspecified"))
      (node (ref "P5") (pin "1") (pinfunction "1_1") (pintype "input"))
      (node (ref "R10") (pin "1") (pinfunction "1_1") (pintype "unspecified"))
      (node (ref "R11") (pin "1") (pinfunction "1_1") (pintype "unspecified"))
      (node (ref "U1") (pin "2") (pinfunction "GND_2") (pintype "unspecified"))
      (node (ref "U2") (pin "1") (pinfunction "GND_1") (pintype "unspecified"))
      (node (ref "U3") (pin "1") (pinfunction "GND_1") (pintype "unspecified"))
      (node (ref "U4") (pin "3") (pinfunction "3_3") (pintype "unspecified"))
      (node (ref "U5") (pin "23") (pinfunction "VSS_1_23") (pintype "unspecified"))
      (node (ref "U5") (pin "35") (pinfunction "VSS_2_35") (pintype "unspecified"))
      (node (ref "U5") (pin "47") (pinfunction "VSS_3_47") (pintype "unspecified"))
      (node (ref "U5") (pin "8") (pinfunction "VSSA_8") (pintype "unspecified"))
      (node (ref "U6") (pin "8") (pinfunction "GND_8") (pintype "unspecified"))
      (node (ref "U7") (pin "8") (pinfunction "GND_8") (pintype "unspecified"))
      (node (ref "USB_TTL1") (pin "4") (pinfunction "GND_4") (pintype "unspecified"))
      (node (ref "USB_TTL1") (pin "5") (pinfunction "GND_5") (pintype "unspecified"))
      (node (ref "USB_TTL1") (pin "6") (pinfunction "GND_6") (pintype "unspecified"))
    )
    (net (code "63") (name "SPINDLE_PWM") (class "Default")
      (node (ref "H6") (pin "1") (pinfunction "1_1") (pintype "input"))
      (node (ref "U5") (pin "29") (pinfunction "PA8_29") (pintype "bidirectional"))
      (node (ref "U7") (pin "6") (pinfunction "IN6_6") (pintype "unspecified"))
    )
    (net (code "64") (name "SWCLK") (class "Default")
      (node (ref "P5") (pin "3") (pinfunction "3_3") (pintype "input"))
      (node (ref "U5") (pin "37") (pinfunction "PA14/JTCK/SWCLK_37") (pintype "bidirectional"))
    )
    (net (code "65") (name "SWDIO") (class "Default")
      (node (ref "P5") (pin "4") (pinfunction "4_4") (pintype "input"))
      (node (ref "U5") (pin "34") (pinfunction "PA13/JTMS/SWDIO_34") (pintype "bidirectional"))
    )
    (net (code "66") (name "TXD") (class "Default")
      (node (ref "R3") (pin "2") (pinfunction "2_2") (pintype "unspecified"))
      (node (ref "U5") (pin "30") (pinfunction "PA9_30") (pintype "bidirectional"))
    )
    (net (code "67") (name "TXD1") (class "Default")
      (node (ref "P1") (pin "2") (pinfunction "2_2") (pintype "unspecified"))
      (node (ref "R3") (pin "1") (pinfunction "1_1") (pintype "unspecified"))
      (node (ref "U2") (pin "3") (pinfunction "RXD_3") (pintype "unspecified"))
    )
    (net (code "68") (name "TXD3") (class "Default")
      (node (ref "P4") (pin "3") (pinfunction "3_3") (pintype "unspecified"))
      (node (ref "U5") (pin "21") (pinfunction "PB10_21") (pintype "bidirectional"))
    )
    (net (code "69") (name "USB_DM") (class "Default")
      (node (ref "U2") (pin "6") (pinfunction "UD-_6") (pintype "unspecified"))
      (node (ref "USB_TTL1") (pin "2") (pinfunction "D-_2") (pintype "unspecified"))
    )
    (net (code "70") (name "USB_DP") (class "Default")
      (node (ref "U2") (pin "5") (pinfunction "UD+_5") (pintype "unspecified"))
      (node (ref "USB_TTL1") (pin "3") (pinfunction "D+_3") (pintype "unspecified"))
    )
    (net (code "71") (name "VIN_24V") (class "Default")
      (node (ref "C3") (pin "1") (pintype "unspecified"))
      (node (ref "C4") (pin "2") (pinfunction "2_2") (pintype "unspecified"))
      (node (ref "D2") (pin "2") (pinfunction "2_2") (pintype "unspecified"))
      (node (ref "R1") (pin "2") (pinfunction "2_2") (pintype "unspecified"))
      (node (ref "U1") (pin "1") (pinfunction "VIN_1") (pintype "unspecified"))
    )
    (net (code "72") (name "VUSB") (class "Default")
      (node (ref "D1") (pin "1") (pinfunction "1_1") (pintype "unspecified"))
      (node (ref "USB_TTL1") (pin "1") (pinfunction "VBUS_1") (pintype "unspecified"))
    )
    (net (code "73") (name "XTAL1") (class "Default")
      (node (ref "C14") (pin "1") (pinfunction "1_1") (pintype "unspecified"))
      (node (ref "U5") (pin "5") (pinfunction "OSC_IN/PD0_5") (pintype "input"))
      (node (ref "Y2") (pin "1") (pinfunction "OSC1_1") (pintype "unspecified"))
    )
    (net (code "74") (name "XTAL2") (class "Default")
      (node (ref "C13") (pin "1") (pinfunction "1_1") (pintype "unspecified"))
      (node (ref "U5") (pin "6") (pinfunction "OSC_OUT/PD1_6") (pintype "output"))
      (node (ref "Y2") (pin "2") (pinfunction "OSC2_2") (pintype "unspecified"))
    )
    (net (code "75") (name "unconnected-(U2-CTS#-Pad9)") (class "Default")
      (node (ref "U2") (pin "9") (pinfunction "CTS#_9") (pintype "unspecified"))
    )
    (net (code "76") (name "unconnected-(U2-DCD#-Pad12)") (class "Default")
      (node (ref "U2") (pin "12") (pinfunction "DCD#_12") (pintype "unspecified"))
    )
    (net (code "77") (name "unconnected-(U2-DSR#-Pad10)") (class "Default")
      (node (ref "U2") (pin "10") (pinfunction "DSR#_10") (pintype "unspecified"))
    )
    (net (code "78") (name "unconnected-(U2-R232-Pad15)") (class "Default")
      (node (ref "U2") (pin "15") (pinfunction "R232_15") (pintype "unspecified"))
    )
    (net (code "79") (name "unconnected-(U2-RI#-Pad11)") (class "Default")
      (node (ref "U2") (pin "11") (pinfunction "RI#_11") (pintype "unspecified"))
    )
    (net (code "80") (name "unconnected-(U2-RTS#-Pad14)") (class "Default")
      (node (ref "U2") (pin "14") (pinfunction "RTS#_14") (pintype "unspecified"))
    )
    (net (code "81") (name "unconnected-(U5-VBAT-Pad1)") (class "Default")
      (node (ref "U5") (pin "1") (pinfunction "VBAT_1") (pintype "unspecified"))
    )
  )
)
